# LiPoCharger.net
KiCad netlist of a schematic drawn in EAGLE
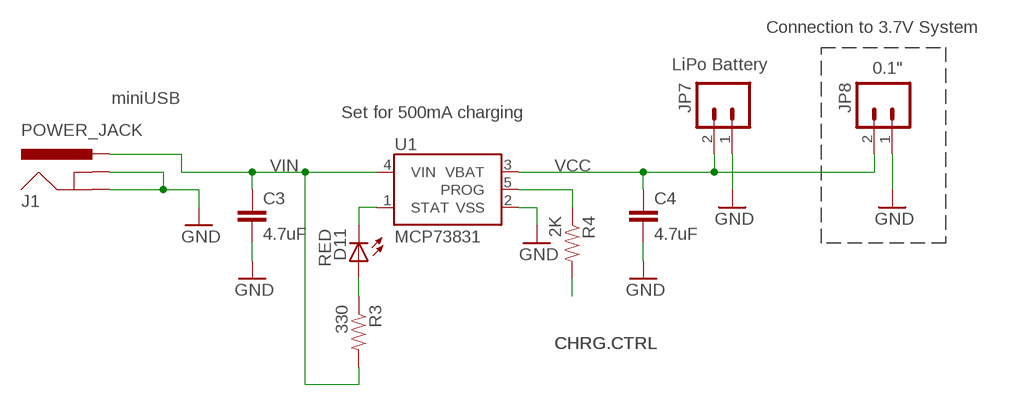
[diagram p0: schematic, sheet 1]

(export (version "E")
  (design (tool "Eeschema 10.0.6"))
  (components
    (comp (ref "C3")
      (value "4.7uF")
      (footprint "eagle-import:0402-CAP")
      (libsource (lib "eagle-import") (part "CAP0402-CAP"))
    )
    (comp (ref "C4")
      (value "4.7uF")
      (footprint "eagle-import:0402-CAP")
      (libsource (lib "eagle-import") (part "CAP0402-CAP"))
    )
    (comp (ref "D11")
      (value "RED")
      (footprint "eagle-import:LED-0603")
      (libsource (lib "eagle-import") (part "LED0603"))
    )
    (comp (ref "J1")
      (value "POWER_JACK")
      (footprint "eagle-import:POWER_JACK_PTH")
      (libsource (lib "eagle-import") (part "POWER_JACK"))
    )
    (comp (ref "JP7")
      (value "LiPo Battery")
      (footprint "eagle-import:JST-2-SMD")
      (libsource (lib "eagle-import") (part "M02-JST-2MM-SMT"))
    )
    (comp (ref "JP8")
      (value "M02PTH")
      (footprint "eagle-import:1X02")
      (libsource (lib "eagle-import") (part "M02PTH"))
    )
    (comp (ref "R3")
      (value "330")
      (footprint "eagle-import:0402-RES")
      (libsource (lib "eagle-import") (part "RESISTOR0402-RES"))
    )
    (comp (ref "R4")
      (value "2K")
      (footprint "eagle-import:0402-RES")
      (libsource (lib "eagle-import") (part "RESISTOR0402-RES"))
    )
    (comp (ref "U1")
      (value "MCP73831")
      (footprint "eagle-import:SOT23-5")
      (libsource (lib "eagle-import") (part "MCP73831"))
    )
  )
  (nets
    (net (code "1") (name "/CHRG.CTRL") (class "Default")
      (node (ref "R4") (pin "2") (pinfunction "2_2") (pintype "passive"))
    )
    (net (code "2") (name "/VCC") (class "Default")
      (node (ref "C4") (pin "1") (pinfunction "1_1") (pintype "passive"))
      (node (ref "JP7") (pin "2") (pinfunction "2_2") (pintype "passive"))
      (node (ref "JP8") (pin "2") (pinfunction "2_2") (pintype "passive"))
      (node (ref "U1") (pin "3") (pinfunction "VBAT_3") (pintype "power_in"))
    )
    (net (code "3") (name "/VIN") (class "Default")
      (node (ref "C3") (pin "1") (pinfunction "1_1") (pintype "passive"))
      (node (ref "J1") (pin "PWR") (pinfunction "PWR_PWR") (pintype "bidirectional"))
      (node (ref "R3") (pin "2") (pinfunction "2_2") (pintype "passive"))
      (node (ref "U1") (pin "4") (pinfunction "VIN_4") (pintype "power_in"))
    )
    (net (code "4") (name "GND") (class "Default")
      (node (ref "C3") (pin "2") (pinfunction "2_2") (pintype "passive"))
      (node (ref "C4") (pin "2") (pinfunction "2_2") (pintype "passive"))
      (node (ref "J1") (pin "GND") (pinfunction "GND_GND") (pintype "bidirectional"))
      (node (ref "J1") (pin "GNDBREAK") (pinfunction "GNDBREAK_GNDBREAK") (pintype "bidirectional"))
      (node (ref "JP7") (pin "1") (pinfunction "1_1") (pintype "passive"))
      (node (ref "JP8") (pin "1") (pinfunction "1_1") (pintype "passive"))
      (node (ref "U1") (pin "2") (pinfunction "VSS_2") (pintype "power_in"))
    )
    (net (code "5") (name "Net-(D11-PadA)") (class "Default")
      (node (ref "D11") (pin "A") (pinfunction "A_A") (pintype "passive"))
      (node (ref "R3") (pin "1") (pinfunction "1_1") (pintype "passive"))
    )
    (net (code "6") (name "Net-(U1-PROG)") (class "Default")
      (node (ref "R4") (pin "1") (pinfunction "1_1") (pintype "passive"))
      (node (ref "U1") (pin "5") (pinfunction "PROG_5") (pintype "input"))
    )
    (net (code "7") (name "Net-(U1-STAT)") (class "Default")
      (node (ref "D11") (pin "C") (pinfunction "C_C") (pintype "passive"))
      (node (ref "U1") (pin "1") (pinfunction "STAT_1") (pintype "output"))
    )
  )
)
